# FEV-60_Motor_uC.net
KiCad netlist of a schematic drawn in Altium Designer
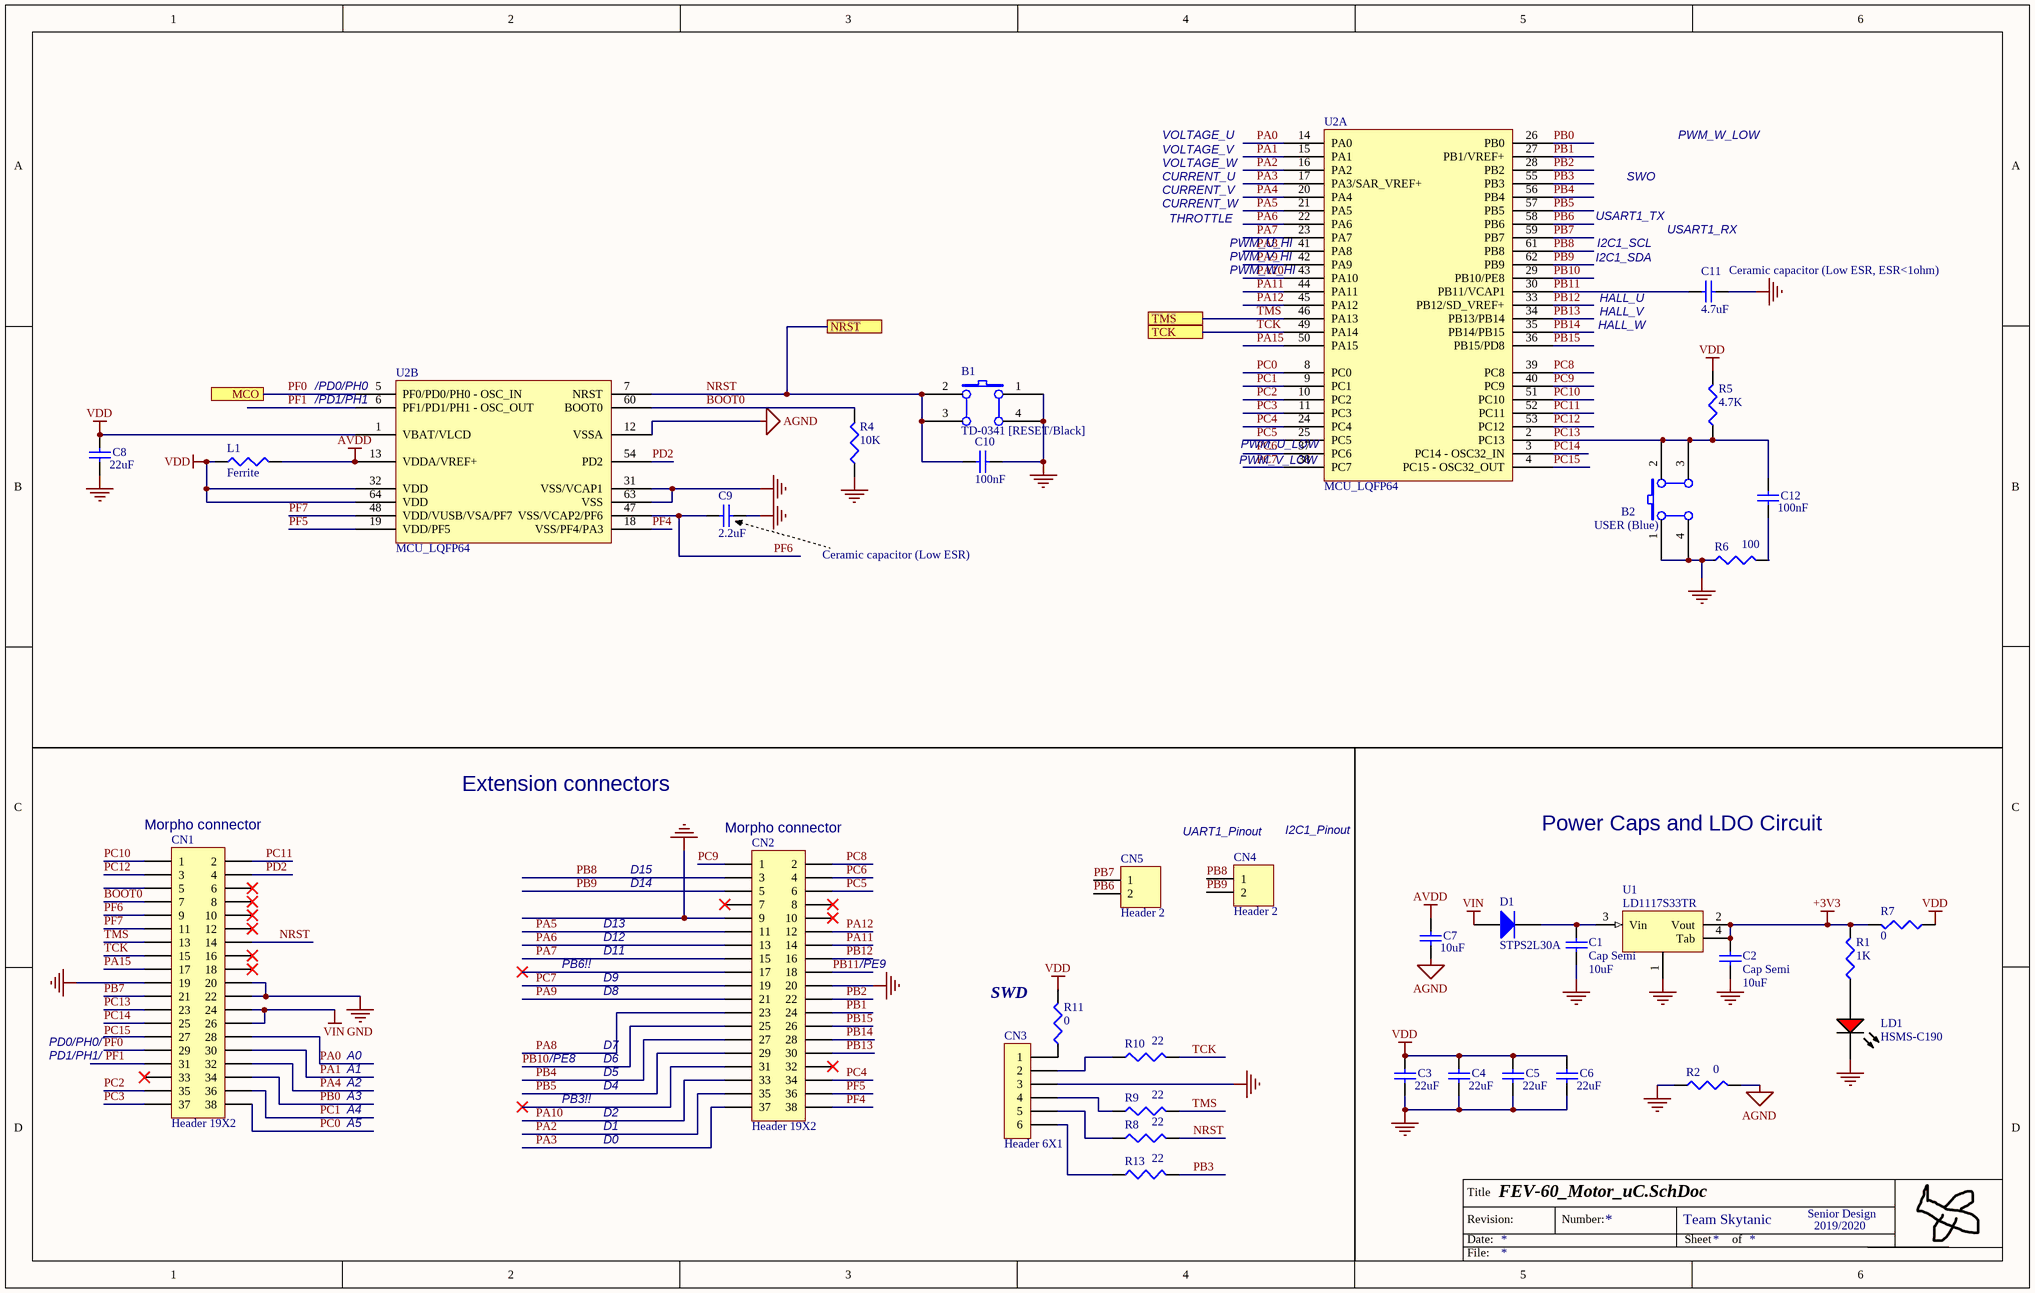
[diagram p0: FEV-60_Motor_uC.SchDoc]

(export (version "E")
  (design (tool "Eeschema 10.0.6"))
  (components
    (comp (ref "B1")
      (value "TD-0341 [RESET/Black]")
      (footprint "Button")
      (description "SE PUSHBUTTON")
      (libsource (lib "Documents") (part "SW PUSHBUTTON"))
    )
    (comp (ref "B2")
      (value "USER (Blue)")
      (footprint "Button")
      (description "SE PUSHBUTTON")
      (libsource (lib "Documents") (part "SW PUSHBUTTON"))
    )
    (comp (ref "C1")
      (value "Cap Semi")
      (footprint "1608[0603]")
      (description "Capacitor (Semiconductor SIM Model)")
      (fields (field (name "ALTIUM_VALUE") "10uF") (field (name "PUBLISHER") "Altium Limited"))
      (libsource (lib "Miscellaneous Devices") (part "Cap Semi"))
    )
    (comp (ref "C2")
      (value "Cap Semi")
      (footprint "1608[0603]")
      (description "Capacitor (Semiconductor SIM Model)")
      (fields (field (name "ALTIUM_VALUE") "10uF") (field (name "PUBLISHER") "Altium Limited"))
      (libsource (lib "Miscellaneous Devices") (part "Cap Semi"))
    )
    (comp (ref "C3")
      (value "22uF")
      (footprint "1608[0603]")
      (description "Capacitor (Semiconductor SIM Model)")
      (fields (field (name "Comment") "Cap Semi") (field (name "PUBLISHER") "Altium Limited"))
      (libsource (lib "Miscellaneous Devices") (part "Cap Semi"))
    )
    (comp (ref "C4")
      (value "22uF")
      (footprint "1608[0603]")
      (description "Capacitor (Semiconductor SIM Model)")
      (fields (field (name "Comment") "Cap Semi") (field (name "PUBLISHER") "Altium Limited"))
      (libsource (lib "Miscellaneous Devices") (part "Cap Semi"))
    )
    (comp (ref "C5")
      (value "22uF")
      (footprint "1608[0603]")
      (description "Capacitor (Semiconductor SIM Model)")
      (fields (field (name "Comment") "Cap Semi") (field (name "PUBLISHER") "Altium Limited"))
      (libsource (lib "Miscellaneous Devices") (part "Cap Semi"))
    )
    (comp (ref "C6")
      (value "22uF")
      (footprint "1608[0603]")
      (description "Capacitor (Semiconductor SIM Model)")
      (fields (field (name "Comment") "Cap Semi") (field (name "PUBLISHER") "Altium Limited"))
      (libsource (lib "Miscellaneous Devices") (part "Cap Semi"))
    )
    (comp (ref "C7")
      (value "10uF")
      (footprint "1608[0603]")
      (description "Capacitor (Semiconductor SIM Model)")
      (fields (field (name "Comment") "Cap Semi") (field (name "PUBLISHER") "Altium Limited"))
      (libsource (lib "Miscellaneous Devices") (part "Cap Semi"))
    )
    (comp (ref "C8")
      (value "22uF")
      (footprint "1608[0603]")
      (description "Capacitor (Semiconductor SIM Model)")
      (fields (field (name "Comment") "Cap Semi") (field (name "PUBLISHER") "Altium Limited"))
      (libsource (lib "Miscellaneous Devices") (part "Cap Semi"))
    )
    (comp (ref "C9")
      (value "2.2uF")
      (footprint "1608[0603]")
      (description "Capacitor (Semiconductor SIM Model)")
      (fields (field (name "Comment") "Cap Semi") (field (name "PUBLISHER") "Altium Limited"))
      (libsource (lib "Miscellaneous Devices") (part "Cap Semi"))
    )
    (comp (ref "C10")
      (value "100nF")
      (footprint "1608[0603]")
      (description "Capacitor (Semiconductor SIM Model)")
      (fields (field (name "Comment") "Cap Semi") (field (name "PUBLISHER") "Altium Limited"))
      (libsource (lib "Miscellaneous Devices") (part "Cap Semi"))
    )
    (comp (ref "C11")
      (value "4.7uF")
      (footprint "1608[0603]")
      (description "Capacitor (Semiconductor SIM Model)")
      (fields (field (name "Comment") "Cap Semi") (field (name "PUBLISHER") "Altium Limited"))
      (libsource (lib "Miscellaneous Devices") (part "Cap Semi"))
    )
    (comp (ref "C12")
      (value "100nF")
      (footprint "1608[0603]")
      (description "Capacitor (Semiconductor SIM Model)")
      (fields (field (name "Comment") "Cap Semi") (field (name "PUBLISHER") "Altium Limited"))
      (libsource (lib "Miscellaneous Devices") (part "Cap Semi"))
    )
    (comp (ref "CN1")
      (value "Header 19X2")
      (footprint "HDR2X19")
      (description "Header, 19-Pin, Dual row")
      (fields (field (name "PUBLISHER") "Altium Limited"))
      (libsource (lib "Nucleo_64_1") (part "Header 19X2"))
    )
    (comp (ref "CN2")
      (value "Header 19X2")
      (footprint "HDR2X19")
      (description "Header, 19-Pin, Dual row")
      (fields (field (name "PUBLISHER") "Altium Limited"))
      (libsource (lib "Nucleo_64_1") (part "Header 19X2"))
    )
    (comp (ref "CN3")
      (value "Header 6X1")
      (footprint "HDR1X6")
      (description "Header, 6-Pin, Single row")
      (fields (field (name "PUBLISHER") "Altium Limited"))
      (libsource (lib "Nucleo_64") (part "Header 6X1"))
    )
    (comp (ref "CN4")
      (value "Header 2")
      (footprint "HDR1X2")
      (description "Header, 2-Pin")
      (fields (field (name "PUBLISHER") "Altium Limited"))
      (libsource (lib "Miscellaneous Connectors") (part "Header 2"))
    )
    (comp (ref "CN5")
      (value "Header 2")
      (footprint "HDR1X2")
      (description "Header, 2-Pin")
      (fields (field (name "PUBLISHER") "Altium Limited"))
      (libsource (lib "Miscellaneous Connectors") (part "Header 2"))
    )
    (comp (ref "D1")
      (value "STPS2L30A")
      (footprint "STPS2L30A")
      (libsource (lib "Nucleo_64") (part "STPS2L30A"))
    )
    (comp (ref "L1")
      (value "Ferrite")
      (footprint "J1-0603")
      (description "Resistor")
      (fields (field (name "PUBLISHER") "Altium Limited"))
      (libsource (lib "Miscellaneous Devices") (part "Res3"))
    )
    (comp (ref "LD1")
      (value "HSMS-C190")
      (footprint "AVAG-HSMX-C190_V")
      (description "LED Uni-Color Red, 52 mW, 20 mA, -40 to 85 degC, 2-Pin SMD, RoHS, Tape and Reel")
      (fields (field (name "MANUFACTURER") "Avago"))
      (libsource (lib "Altium Content Vault") (part "LED-RED-AK-2"))
    )
    (comp (ref "R1")
      (value "1K")
      (footprint "J1-0603")
      (description "Resistor")
      (fields (field (name "Comment") "Res3") (field (name "PUBLISHER") "Altium Limited"))
      (libsource (lib "Miscellaneous Devices") (part "Res3"))
    )
    (comp (ref "R2")
      (value "0")
      (footprint "J1-0603")
      (description "Resistor")
      (fields (field (name "Comment") "Res3") (field (name "PUBLISHER") "Altium Limited"))
      (libsource (lib "Miscellaneous Devices") (part "Res3"))
    )
    (comp (ref "R4")
      (value "10K")
      (footprint "J1-0603")
      (description "Resistor")
      (fields (field (name "Comment") "Res3") (field (name "PUBLISHER") "Altium Limited"))
      (libsource (lib "Miscellaneous Devices") (part "Res3"))
    )
    (comp (ref "R5")
      (value "4.7K")
      (footprint "J1-0603")
      (description "Resistor")
      (fields (field (name "Comment") "Res3") (field (name "PUBLISHER") "Altium Limited"))
      (libsource (lib "Miscellaneous Devices") (part "Res3"))
    )
    (comp (ref "R6")
      (value "100")
      (footprint "J1-0603")
      (description "Resistor")
      (fields (field (name "Comment") "Res3") (field (name "PUBLISHER") "Altium Limited"))
      (libsource (lib "Miscellaneous Devices") (part "Res3"))
    )
    (comp (ref "R7")
      (value "0")
      (footprint "J1-0603")
      (description "Resistor")
      (fields (field (name "Comment") "Res3") (field (name "PUBLISHER") "Altium Limited"))
      (libsource (lib "Miscellaneous Devices") (part "Res3"))
    )
    (comp (ref "R8")
      (value "22")
      (footprint "J1-0603")
      (description "Resistor")
      (fields (field (name "Comment") "Res3") (field (name "PUBLISHER") "Altium Limited"))
      (libsource (lib "Miscellaneous Devices") (part "Res3"))
    )
    (comp (ref "R9")
      (value "22")
      (footprint "J1-0603")
      (description "Resistor")
      (fields (field (name "Comment") "Res3") (field (name "PUBLISHER") "Altium Limited"))
      (libsource (lib "Miscellaneous Devices") (part "Res3"))
    )
    (comp (ref "R10")
      (value "22")
      (footprint "J1-0603")
      (description "Resistor")
      (fields (field (name "Comment") "Res3") (field (name "PUBLISHER") "Altium Limited"))
      (libsource (lib "Miscellaneous Devices") (part "Res3"))
    )
    (comp (ref "R11")
      (value "0")
      (footprint "J1-0603")
      (description "Resistor")
      (fields (field (name "Comment") "Res3") (field (name "PUBLISHER") "Altium Limited"))
      (libsource (lib "Miscellaneous Devices") (part "Res3"))
    )
    (comp (ref "R13")
      (value "22")
      (footprint "J1-0603")
      (description "Resistor")
      (fields (field (name "Comment") "Res3") (field (name "PUBLISHER") "Altium Limited"))
      (libsource (lib "Miscellaneous Devices") (part "Res3"))
    )
    (comp (ref "U1")
      (value "LD1117S33TR")
      (footprint "LD1117S33TR")
      (libsource (lib "mb1045") (part "LD1117"))
    )
    (comp (ref "U2")
      (value "MCU_LQFP64")
      (footprint "STM32F030R8")
      (libsource (lib "Nucleo_64") (part "MCU_LQFP64"))
    )
  )
  (nets
    (net (code "1") (name "+3V3") (class "Default")
      (node (ref "C2") (pin "2") (pinfunction "2_2") (pintype "passive"))
      (node (ref "R1") (pin "2") (pinfunction "2_2") (pintype "passive"))
      (node (ref "R7") (pin "2") (pinfunction "2_2") (pintype "passive"))
      (node (ref "U1") (pin "2") (pinfunction "Vout_2") (pintype "power_in"))
      (node (ref "U1") (pin "4") (pinfunction "Tab_4") (pintype "power_in"))
    )
    (net (code "2") (name "/BOOT0") (class "Default")
      (node (ref "CN1") (pin "7") (pinfunction "7_7") (pintype "passive"))
      (node (ref "R4") (pin "2") (pinfunction "2_2") (pintype "passive"))
      (node (ref "U2") (pin "60") (pinfunction "BOOT0_60") (pintype "passive"))
    )
    (net (code "3") (name "/NRST") (class "Default")
      (node (ref "B1") (pin "2") (pinfunction "B0_2") (pintype "passive"))
      (node (ref "B1") (pin "3") (pinfunction "B1_3") (pintype "passive"))
      (node (ref "C10") (pin "2") (pinfunction "2_2") (pintype "passive"))
      (node (ref "CN1") (pin "14") (pinfunction "14_14") (pintype "passive"))
      (node (ref "R8") (pin "2") (pinfunction "2_2") (pintype "passive"))
      (node (ref "U2") (pin "7") (pinfunction "NRST_7") (pintype "passive"))
    )
    (net (code "4") (name "/PA0") (class "Default")
      (node (ref "CN1") (pin "28") (pinfunction "28_28") (pintype "passive"))
      (node (ref "U2") (pin "14") (pinfunction "PA0_14") (pintype "passive"))
    )
    (net (code "5") (name "/PA1") (class "Default")
      (node (ref "CN1") (pin "30") (pinfunction "30_30") (pintype "passive"))
      (node (ref "U2") (pin "15") (pinfunction "PA1_15") (pintype "passive"))
    )
    (net (code "6") (name "/PA2") (class "Default")
      (node (ref "CN2") (pin "35") (pinfunction "35_35") (pintype "passive"))
      (node (ref "U2") (pin "16") (pinfunction "PA2_16") (pintype "passive"))
    )
    (net (code "7") (name "/PA3") (class "Default")
      (node (ref "CN2") (pin "37") (pinfunction "37_37") (pintype "passive"))
      (node (ref "U2") (pin "17") (pinfunction "PA3/SAR_VREF+_17") (pintype "passive"))
    )
    (net (code "8") (name "/PA4") (class "Default")
      (node (ref "CN1") (pin "32") (pinfunction "32_32") (pintype "passive"))
      (node (ref "U2") (pin "20") (pinfunction "PA4_20") (pintype "passive"))
    )
    (net (code "9") (name "/PA5") (class "Default")
      (node (ref "CN2") (pin "11") (pinfunction "11_11") (pintype "passive"))
      (node (ref "U2") (pin "21") (pinfunction "PA5_21") (pintype "passive"))
    )
    (net (code "10") (name "/PA6") (class "Default")
      (node (ref "CN2") (pin "13") (pinfunction "13_13") (pintype "passive"))
      (node (ref "U2") (pin "22") (pinfunction "PA6_22") (pintype "passive"))
    )
    (net (code "11") (name "/PA7") (class "Default")
      (node (ref "CN2") (pin "15") (pinfunction "15_15") (pintype "passive"))
      (node (ref "U2") (pin "23") (pinfunction "PA7_23") (pintype "passive"))
    )
    (net (code "12") (name "/PA8") (class "Default")
      (node (ref "CN2") (pin "23") (pinfunction "23_23") (pintype "passive"))
      (node (ref "U2") (pin "41") (pinfunction "PA8_41") (pintype "passive"))
    )
    (net (code "13") (name "/PA9") (class "Default")
      (node (ref "CN2") (pin "21") (pinfunction "21_21") (pintype "passive"))
      (node (ref "U2") (pin "42") (pinfunction "PA9_42") (pintype "passive"))
    )
    (net (code "14") (name "/PA10") (class "Default")
      (node (ref "CN2") (pin "33") (pinfunction "33_33") (pintype "passive"))
      (node (ref "U2") (pin "43") (pinfunction "PA10_43") (pintype "passive"))
    )
    (net (code "15") (name "/PA11") (class "Default")
      (node (ref "CN2") (pin "14") (pinfunction "14_14") (pintype "passive"))
      (node (ref "U2") (pin "44") (pinfunction "PA11_44") (pintype "passive"))
    )
    (net (code "16") (name "/PA12") (class "Default")
      (node (ref "CN2") (pin "12") (pinfunction "12_12") (pintype "passive"))
      (node (ref "U2") (pin "45") (pinfunction "PA12_45") (pintype "passive"))
    )
    (net (code "17") (name "/PA15") (class "Default")
      (node (ref "CN1") (pin "17") (pinfunction "17_17") (pintype "passive"))
      (node (ref "U2") (pin "50") (pinfunction "PA15_50") (pintype "passive"))
    )
    (net (code "18") (name "/PB0") (class "Default")
      (node (ref "CN1") (pin "34") (pinfunction "34_34") (pintype "passive"))
      (node (ref "U2") (pin "26") (pinfunction "PB0_26") (pintype "passive"))
    )
    (net (code "19") (name "/PB1") (class "Default")
      (node (ref "CN2") (pin "24") (pinfunction "24_24") (pintype "passive"))
      (node (ref "U2") (pin "27") (pinfunction "PB1/VREF+_27") (pintype "passive"))
    )
    (net (code "20") (name "/PB2") (class "Default")
      (node (ref "CN2") (pin "22") (pinfunction "22_22") (pintype "passive"))
      (node (ref "U2") (pin "28") (pinfunction "PB2_28") (pintype "passive"))
    )
    (net (code "21") (name "/PB3") (class "Default")
      (node (ref "R13") (pin "2") (pinfunction "2_2") (pintype "passive"))
      (node (ref "U2") (pin "55") (pinfunction "PB3_55") (pintype "passive"))
    )
    (net (code "22") (name "/PB4") (class "Default")
      (node (ref "CN2") (pin "27") (pinfunction "27_27") (pintype "passive"))
      (node (ref "U2") (pin "56") (pinfunction "PB4_56") (pintype "passive"))
    )
    (net (code "23") (name "/PB5") (class "Default")
      (node (ref "CN2") (pin "29") (pinfunction "29_29") (pintype "passive"))
      (node (ref "U2") (pin "57") (pinfunction "PB5_57") (pintype "passive"))
    )
    (net (code "24") (name "/PB6") (class "Default")
      (node (ref "CN5") (pin "2") (pinfunction "2_2") (pintype "passive"))
      (node (ref "U2") (pin "58") (pinfunction "PB6_58") (pintype "passive"))
    )
    (net (code "25") (name "/PB7") (class "Default")
      (node (ref "CN1") (pin "21") (pinfunction "21_21") (pintype "passive"))
      (node (ref "CN5") (pin "1") (pinfunction "1_1") (pintype "passive"))
      (node (ref "U2") (pin "59") (pinfunction "PB7_59") (pintype "passive"))
    )
    (net (code "26") (name "/PB8") (class "Default")
      (node (ref "CN2") (pin "3") (pinfunction "3_3") (pintype "passive"))
      (node (ref "CN4") (pin "1") (pinfunction "1_1") (pintype "passive"))
      (node (ref "U2") (pin "61") (pinfunction "PB8_61") (pintype "passive"))
    )
    (net (code "27") (name "/PB9") (class "Default")
      (node (ref "CN2") (pin "5") (pinfunction "5_5") (pintype "passive"))
      (node (ref "CN4") (pin "2") (pinfunction "2_2") (pintype "passive"))
      (node (ref "U2") (pin "62") (pinfunction "PB9_62") (pintype "passive"))
    )
    (net (code "28") (name "/PB10") (class "Default")
      (node (ref "CN2") (pin "25") (pinfunction "25_25") (pintype "passive"))
      (node (ref "U2") (pin "29") (pinfunction "PB10/PE8_29") (pintype "passive"))
    )
    (net (code "29") (name "/PB11") (class "Default")
      (node (ref "C11") (pin "2") (pinfunction "2_2") (pintype "passive"))
      (node (ref "CN2") (pin "18") (pinfunction "18_18") (pintype "passive"))
      (node (ref "U2") (pin "30") (pinfunction "PB11/VCAP1_30") (pintype "passive"))
    )
    (net (code "30") (name "/PB12") (class "Default")
      (node (ref "CN2") (pin "16") (pinfunction "16_16") (pintype "passive"))
      (node (ref "U2") (pin "33") (pinfunction "PB12/SD_VREF+_33") (pintype "passive"))
    )
    (net (code "31") (name "/PB13") (class "Default")
      (node (ref "CN2") (pin "30") (pinfunction "30_30") (pintype "passive"))
      (node (ref "U2") (pin "34") (pinfunction "PB13/PB14_34") (pintype "passive"))
    )
    (net (code "32") (name "/PB14") (class "Default")
      (node (ref "CN2") (pin "28") (pinfunction "28_28") (pintype "passive"))
      (node (ref "U2") (pin "35") (pinfunction "PB14/PB15_35") (pintype "passive"))
    )
    (net (code "33") (name "/PB15") (class "Default")
      (node (ref "CN2") (pin "26") (pinfunction "26_26") (pintype "passive"))
      (node (ref "U2") (pin "36") (pinfunction "PB15/PD8_36") (pintype "passive"))
    )
    (net (code "34") (name "/PC0") (class "Default")
      (node (ref "CN1") (pin "38") (pinfunction "38_38") (pintype "passive"))
      (node (ref "U2") (pin "8") (pinfunction "PC0_8") (pintype "passive"))
    )
    (net (code "35") (name "/PC1") (class "Default")
      (node (ref "CN1") (pin "36") (pinfunction "36_36") (pintype "passive"))
      (node (ref "U2") (pin "9") (pinfunction "PC1_9") (pintype "passive"))
    )
    (net (code "36") (name "/PC2") (class "Default")
      (node (ref "CN1") (pin "35") (pinfunction "35_35") (pintype "passive"))
      (node (ref "U2") (pin "10") (pinfunction "PC2_10") (pintype "passive"))
    )
    (net (code "37") (name "/PC3") (class "Default")
      (node (ref "CN1") (pin "37") (pinfunction "37_37") (pintype "passive"))
      (node (ref "U2") (pin "11") (pinfunction "PC3_11") (pintype "passive"))
    )
    (net (code "38") (name "/PC4") (class "Default")
      (node (ref "CN2") (pin "34") (pinfunction "34_34") (pintype "passive"))
      (node (ref "U2") (pin "24") (pinfunction "PC4_24") (pintype "passive"))
    )
    (net (code "39") (name "/PC5") (class "Default")
      (node (ref "CN2") (pin "6") (pinfunction "6_6") (pintype "passive"))
      (node (ref "U2") (pin "25") (pinfunction "PC5_25") (pintype "passive"))
    )
    (net (code "40") (name "/PC6") (class "Default")
      (node (ref "CN2") (pin "4") (pinfunction "4_4") (pintype "passive"))
      (node (ref "U2") (pin "37") (pinfunction "PC6_37") (pintype "passive"))
    )
    (net (code "41") (name "/PC7") (class "Default")
      (node (ref "CN2") (pin "19") (pinfunction "19_19") (pintype "passive"))
      (node (ref "U2") (pin "38") (pinfunction "PC7_38") (pintype "passive"))
    )
    (net (code "42") (name "/PC8") (class "Default")
      (node (ref "CN2") (pin "2") (pinfunction "2_2") (pintype "passive"))
      (node (ref "U2") (pin "39") (pinfunction "PC8_39") (pintype "passive"))
    )
    (net (code "43") (name "/PC9") (class "Default")
      (node (ref "CN2") (pin "1") (pinfunction "1_1") (pintype "passive"))
      (node (ref "U2") (pin "40") (pinfunction "PC9_40") (pintype "passive"))
    )
    (net (code "44") (name "/PC10") (class "Default")
      (node (ref "CN1") (pin "1") (pinfunction "1_1") (pintype "passive"))
      (node (ref "U2") (pin "51") (pinfunction "PC10_51") (pintype "passive"))
    )
    (net (code "45") (name "/PC11") (class "Default")
      (node (ref "CN1") (pin "2") (pinfunction "2_2") (pintype "passive"))
      (node (ref "U2") (pin "52") (pinfunction "PC11_52") (pintype "passive"))
    )
    (net (code "46") (name "/PC12") (class "Default")
      (node (ref "CN1") (pin "3") (pinfunction "3_3") (pintype "passive"))
      (node (ref "U2") (pin "53") (pinfunction "PC12_53") (pintype "passive"))
    )
    (net (code "47") (name "/PC13") (class "Default")
      (node (ref "B2") (pin "2") (pinfunction "B0_2") (pintype "passive"))
      (node (ref "B2") (pin "3") (pinfunction "B1_3") (pintype "passive"))
      (node (ref "C12") (pin "2") (pinfunction "2_2") (pintype "passive"))
      (node (ref "CN1") (pin "23") (pinfunction "23_23") (pintype "passive"))
      (node (ref "R5") (pin "1") (pinfunction "1_1") (pintype "passive"))
      (node (ref "U2") (pin "2") (pinfunction "PC13_2") (pintype "passive"))
    )
    (net (code "48") (name "/PC14") (class "Default")
      (node (ref "CN1") (pin "25") (pinfunction "25_25") (pintype "passive"))
      (node (ref "U2") (pin "3") (pinfunction "PC14_-_OSC32_IN_3") (pintype "passive"))
    )
    (net (code "49") (name "/PC15") (class "Default")
      (node (ref "CN1") (pin "27") (pinfunction "27_27") (pintype "passive"))
      (node (ref "U2") (pin "4") (pinfunction "PC15_-_OSC32_OUT_4") (pintype "passive"))
    )
    (net (code "50") (name "/PD2") (class "Default")
      (node (ref "CN1") (pin "4") (pinfunction "4_4") (pintype "passive"))
      (node (ref "U2") (pin "54") (pinfunction "PD2_54") (pintype "passive"))
    )
    (net (code "51") (name "/PF0") (class "Default")
      (node (ref "CN1") (pin "29") (pinfunction "29_29") (pintype "passive"))
      (node (ref "U2") (pin "5") (pinfunction "PF0/PD0/PH0_-_OSC_IN_5") (pintype "passive"))
    )
    (net (code "52") (name "/PF1") (class "Default")
      (node (ref "CN1") (pin "31") (pinfunction "31_31") (pintype "passive"))
      (node (ref "U2") (pin "6") (pinfunction "PF1/PD1/PH1_-_OSC_OUT_6") (pintype "passive"))
    )
    (net (code "53") (name "/PF4") (class "Default")
      (node (ref "CN2") (pin "38") (pinfunction "38_38") (pintype "passive"))
      (node (ref "U2") (pin "18") (pinfunction "VSS/PF4/PA3_18") (pintype "passive"))
    )
    (net (code "54") (name "/PF5") (class "Default")
      (node (ref "CN2") (pin "36") (pinfunction "36_36") (pintype "passive"))
      (node (ref "U2") (pin "19") (pinfunction "VDD/PF5_19") (pintype "passive"))
    )
    (net (code "55") (name "/PF6") (class "Default")
      (node (ref "C9") (pin "2") (pinfunction "2_2") (pintype "passive"))
      (node (ref "CN1") (pin "9") (pinfunction "9_9") (pintype "passive"))
      (node (ref "U2") (pin "47") (pinfunction "VSS/VCAP2/PF6_47") (pintype "passive"))
    )
    (net (code "56") (name "/PF7") (class "Default")
      (node (ref "CN1") (pin "11") (pinfunction "11_11") (pintype "passive"))
      (node (ref "U2") (pin "48") (pinfunction "VDD/VUSB/VSA/PF7_48") (pintype "passive"))
    )
    (net (code "57") (name "/TCK") (class "Default")
      (node (ref "CN1") (pin "15") (pinfunction "15_15") (pintype "passive"))
      (node (ref "R10") (pin "2") (pinfunction "2_2") (pintype "passive"))
      (node (ref "U2") (pin "49") (pinfunction "PA14_49") (pintype "passive"))
    )
    (net (code "58") (name "/TMS") (class "Default")
      (node (ref "CN1") (pin "13") (pinfunction "13_13") (pintype "passive"))
      (node (ref "R9") (pin "2") (pinfunction "2_2") (pintype "passive"))
      (node (ref "U2") (pin "46") (pinfunction "PA13_46") (pintype "passive"))
    )
    (net (code "59") (name "AGND") (class "Default")
      (node (ref "C7") (pin "1") (pinfunction "1_1") (pintype "passive"))
      (node (ref "R2") (pin "2") (pinfunction "2_2") (pintype "passive"))
      (node (ref "U2") (pin "12") (pinfunction "VSSA_12") (pintype "passive"))
    )
    (net (code "60") (name "AVDD") (class "Default")
      (node (ref "C7") (pin "2") (pinfunction "2_2") (pintype "passive"))
      (node (ref "L1") (pin "2") (pinfunction "2_2") (pintype "passive"))
      (node (ref "U2") (pin "13") (pinfunction "VDDA/VREF+_13") (pintype "passive"))
    )
    (net (code "61") (name "GND") (class "Default")
      (node (ref "B1") (pin "1") (pinfunction "A0_1") (pintype "passive"))
      (node (ref "B1") (pin "4") (pinfunction "A1_4") (pintype "passive"))
      (node (ref "B2") (pin "1") (pinfunction "A0_1") (pintype "passive"))
      (node (ref "B2") (pin "4") (pinfunction "A1_4") (pintype "passive"))
      (node (ref "C1") (pin "1") (pinfunction "1_1") (pintype "passive"))
      (node (ref "C10") (pin "1") (pinfunction "1_1") (pintype "passive"))
      (node (ref "C11") (pin "1") (pinfunction "1_1") (pintype "passive"))
      (node (ref "C2") (pin "1") (pinfunction "1_1") (pintype "passive"))
      (node (ref "C3") (pin "1") (pinfunction "1_1") (pintype "passive"))
      (node (ref "C4") (pin "1") (pinfunction "1_1") (pintype "passive"))
      (node (ref "C5") (pin "1") (pinfunction "1_1") (pintype "passive"))
      (node (ref "C6") (pin "1") (pinfunction "1_1") (pintype "passive"))
      (node (ref "C8") (pin "1") (pinfunction "1_1") (pintype "passive"))
      (node (ref "C9") (pin "1") (pinfunction "1_1") (pintype "passive"))
      (node (ref "CN1") (pin "19") (pinfunction "19_19") (pintype "passive"))
      (node (ref "CN1") (pin "20") (pinfunction "20_20") (pintype "passive"))
      (node (ref "CN1") (pin "22") (pinfunction "22_22") (pintype "passive"))
      (node (ref "CN2") (pin "20") (pinfunction "20_20") (pintype "passive"))
      (node (ref "CN2") (pin "9") (pinfunction "9_9") (pintype "passive"))
      (node (ref "CN3") (pin "3") (pinfunction "3_3") (pintype "passive"))
      (node (ref "LD1") (pin "2") (pinfunction "K_2") (pintype "passive"))
      (node (ref "R2") (pin "1") (pinfunction "1_1") (pintype "passive"))
      (node (ref "R4") (pin "1") (pinfunction "1_1") (pintype "passive"))
      (node (ref "R6") (pin "1") (pinfunction "1_1") (pintype "passive"))
      (node (ref "U1") (pin "1") (pintype "passive"))
      (node (ref "U2") (pin "31") (pinfunction "VSS/VCAP1_31") (pintype "passive"))
      (node (ref "U2") (pin "63") (pinfunction "VSS_63") (pintype "passive"))
    )
    (net (code "62") (name "Net-(C12-Pad1)") (class "Default")
      (node (ref "C12") (pin "1") (pinfunction "1_1") (pintype "passive"))
      (node (ref "R6") (pin "2") (pinfunction "2_2") (pintype "passive"))
    )
    (net (code "63") (name "Net-(CN3-Pad1)") (class "Default")
      (node (ref "CN3") (pin "1") (pinfunction "1_1") (pintype "passive"))
      (node (ref "R11") (pin "1") (pinfunction "1_1") (pintype "passive"))
    )
    (net (code "64") (name "Net-(CN3-Pad2)") (class "Default")
      (node (ref "CN3") (pin "2") (pinfunction "2_2") (pintype "passive"))
      (node (ref "R10") (pin "1") (pinfunction "1_1") (pintype "passive"))
    )
    (net (code "65") (name "Net-(CN3-Pad4)") (class "Default")
      (node (ref "CN3") (pin "4") (pinfunction "4_4") (pintype "passive"))
      (node (ref "R9") (pin "1") (pinfunction "1_1") (pintype "passive"))
    )
    (net (code "66") (name "Net-(CN3-Pad5)") (class "Default")
      (node (ref "CN3") (pin "5") (pinfunction "5_5") (pintype "passive"))
      (node (ref "R8") (pin "1") (pinfunction "1_1") (pintype "passive"))
    )
    (net (code "67") (name "Net-(CN3-Pad6)") (class "Default")
      (node (ref "CN3") (pin "6") (pinfunction "6_6") (pintype "passive"))
      (node (ref "R13") (pin "1") (pinfunction "1_1") (pintype "passive"))
    )
    (net (code "68") (name "Net-(D1-K)") (class "Default")
      (node (ref "C1") (pin "2") (pinfunction "2_2") (pintype "passive"))
      (node (ref "D1") (pin "2") (pinfunction "K_2") (pintype "passive"))
      (node (ref "U1") (pin "3") (pinfunction "Vin_3") (pintype "input"))
    )
    (net (code "69") (name "Net-(LD1-A)") (class "Default")
      (node (ref "LD1") (pin "1") (pinfunction "A_1") (pintype "passive"))
      (node (ref "R1") (pin "1") (pinfunction "1_1") (pintype "passive"))
    )
    (net (code "70") (name "VDD") (class "Default")
      (node (ref "C3") (pin "2") (pinfunction "2_2") (pintype "passive"))
      (node (ref "C4") (pin "2") (pinfunction "2_2") (pintype "passive"))
      (node (ref "C5") (pin "2") (pinfunction "2_2") (pintype "passive"))
      (node (ref "C6") (pin "2") (pinfunction "2_2") (pintype "passive"))
      (node (ref "C8") (pin "2") (pinfunction "2_2") (pintype "passive"))
      (node (ref "L1") (pin "1") (pinfunction "1_1") (pintype "passive"))
      (node (ref "R11") (pin "2") (pinfunction "2_2") (pintype "passive"))
      (node (ref "R5") (pin "2") (pinfunction "2_2") (pintype "passive"))
      (node (ref "R7") (pin "1") (pinfunction "1_1") (pintype "passive"))
      (node (ref "U2") (pin "1") (pinfunction "VBAT/VLCD_1") (pintype "passive"))
      (node (ref "U2") (pin "32") (pinfunction "VDD_32") (pintype "passive"))
      (node (ref "U2") (pin "64") (pinfunction "VDD_64") (pintype "passive"))
    )
    (net (code "71") (name "VIN") (class "Default")
      (node (ref "CN1") (pin "24") (pinfunction "24_24") (pintype "passive"))
      (node (ref "CN1") (pin "26") (pinfunction "26_26") (pintype "passive"))
      (node (ref "D1") (pin "1") (pinfunction "A_1") (pintype "passive"))
    )
    (net (code "72") (name "unconnected-(CN1-Pad5)") (class "Default")
      (node (ref "CN1") (pin "5") (pinfunction "5_5") (pintype "passive"))
    )
    (net (code "73") (name "unconnected-(CN1-Pad6)") (class "Default")
      (node (ref "CN1") (pin "6") (pinfunction "6_6") (pintype "passive+no_connect"))
    )
    (net (code "74") (name "unconnected-(CN1-Pad8)") (class "Default")
      (node (ref "CN1") (pin "8") (pinfunction "8_8") (pintype "passive+no_connect"))
    )
    (net (code "75") (name "unconnected-(CN1-Pad10)") (class "Default")
      (node (ref "CN1") (pin "10") (pinfunction "10_10") (pintype "passive+no_connect"))
    )
    (net (code "76") (name "unconnected-(CN1-Pad12)") (class "Default")
      (node (ref "CN1") (pin "12") (pinfunction "12_12") (pintype "passive+no_connect"))
    )
    (net (code "77") (name "unconnected-(CN1-Pad16)") (class "Default")
      (node (ref "CN1") (pin "16") (pinfunction "16_16") (pintype "passive+no_connect"))
    )
    (net (code "78") (name "unconnected-(CN1-Pad18)") (class "Default")
      (node (ref "CN1") (pin "18") (pinfunction "18_18") (pintype "passive+no_connect"))
    )
    (net (code "79") (name "unconnected-(CN1-Pad33)") (class "Default")
      (node (ref "CN1") (pin "33") (pinfunction "33_33") (pintype "passive+no_connect"))
    )
    (net (code "80") (name "unconnected-(CN2-Pad7)") (class "Default")
      (node (ref "CN2") (pin "7") (pinfunction "7_7") (pintype "passive+no_connect"))
    )
    (net (code "81") (name "unconnected-(CN2-Pad8)") (class "Default")
      (node (ref "CN2") (pin "8") (pinfunction "8_8") (pintype "passive+no_connect"))
    )
    (net (code "82") (name "unconnected-(CN2-Pad10)") (class "Default")
      (node (ref "CN2") (pin "10") (pinfunction "10_10") (pintype "passive+no_connect"))
    )
    (net (code "83") (name "unconnected-(CN2-Pad17)") (class "Default")
      (node (ref "CN2") (pin "17") (pinfunction "17_17") (pintype "passive+no_connect"))
    )
    (net (code "84") (name "unconnected-(CN2-Pad31)") (class "Default")
      (node (ref "CN2") (pin "31") (pinfunction "31_31") (pintype "passive+no_connect"))
    )
    (net (code "85") (name "unconnected-(CN2-Pad32)") (class "Default")
      (node (ref "CN2") (pin "32") (pinfunction "32_32") (pintype "passive+no_connect"))
    )
  )
)
